# sens.net
KiCad netlist of a schematic drawn in EAGLE
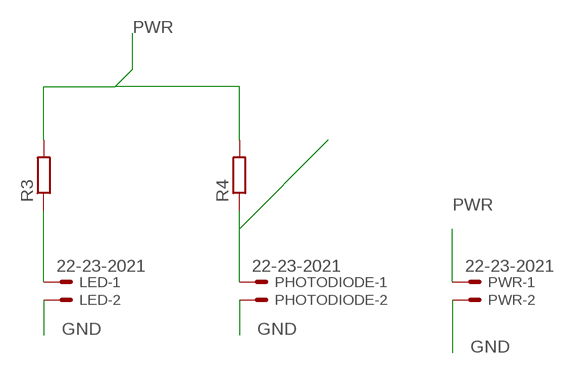
[diagram p0: schematic, sheet 1]

(export (version "E")
  (design (tool "Eeschema 10.0.6"))
  (components
    (comp (ref "LED")
      (value "22-23-2021")
      (footprint "eagle-import:22-23-2021")
      (fields (field (name "MF") "MOLEX"))
      (libsource (lib "eagle-import") (part "22-23-2021"))
    )
    (comp (ref "PHOTODIODE")
      (value "22-23-2021")
      (footprint "eagle-import:22-23-2021")
      (fields (field (name "MF") "MOLEX"))
      (libsource (lib "eagle-import") (part "22-23-2021"))
    )
    (comp (ref "PWR")
      (value "22-23-2021")
      (footprint "eagle-import:22-23-2021")
      (fields (field (name "MF") "MOLEX"))
      (libsource (lib "eagle-import") (part "22-23-2021"))
    )
    (comp (ref "R3")
      (value "R-EU_0207/7")
      (footprint "eagle-import:0207_7")
      (libsource (lib "eagle-import") (part "R-EU_0207/7"))
    )
    (comp (ref "R4")
      (value "R-EU_0207/7")
      (footprint "eagle-import:0207_7")
      (libsource (lib "eagle-import") (part "R-EU_0207/7"))
    )
  )
  (nets
    (net (code "1") (name "/GND") (class "Default")
      (node (ref "LED") (pin "2") (pinfunction "S_2") (pintype "passive"))
      (node (ref "PHOTODIODE") (pin "2") (pinfunction "S_2") (pintype "passive"))
      (node (ref "PWR") (pin "2") (pinfunction "S_2") (pintype "passive"))
    )
    (net (code "2") (name "/PWR") (class "Default")
      (node (ref "PWR") (pin "1") (pinfunction "S_1") (pintype "passive"))
      (node (ref "R3") (pin "2") (pinfunction "2_2") (pintype "passive"))
      (node (ref "R4") (pin "2") (pinfunction "2_2") (pintype "passive"))
    )
    (net (code "3") (name "Net-(LEDA-S)") (class "Default")
      (node (ref "LED") (pin "1") (pinfunction "S_1") (pintype "passive"))
      (node (ref "R3") (pin "1") (pinfunction "1_1") (pintype "passive"))
    )
    (net (code "4") (name "Net-(PHOTODIODEA-S)") (class "Default")
      (node (ref "PHOTODIODE") (pin "1") (pinfunction "S_1") (pintype "passive"))
      (node (ref "R4") (pin "1") (pinfunction "1_1") (pintype "passive"))
    )
  )
)
